# schematic.net
KiCad netlist of a schematic drawn in EAGLE
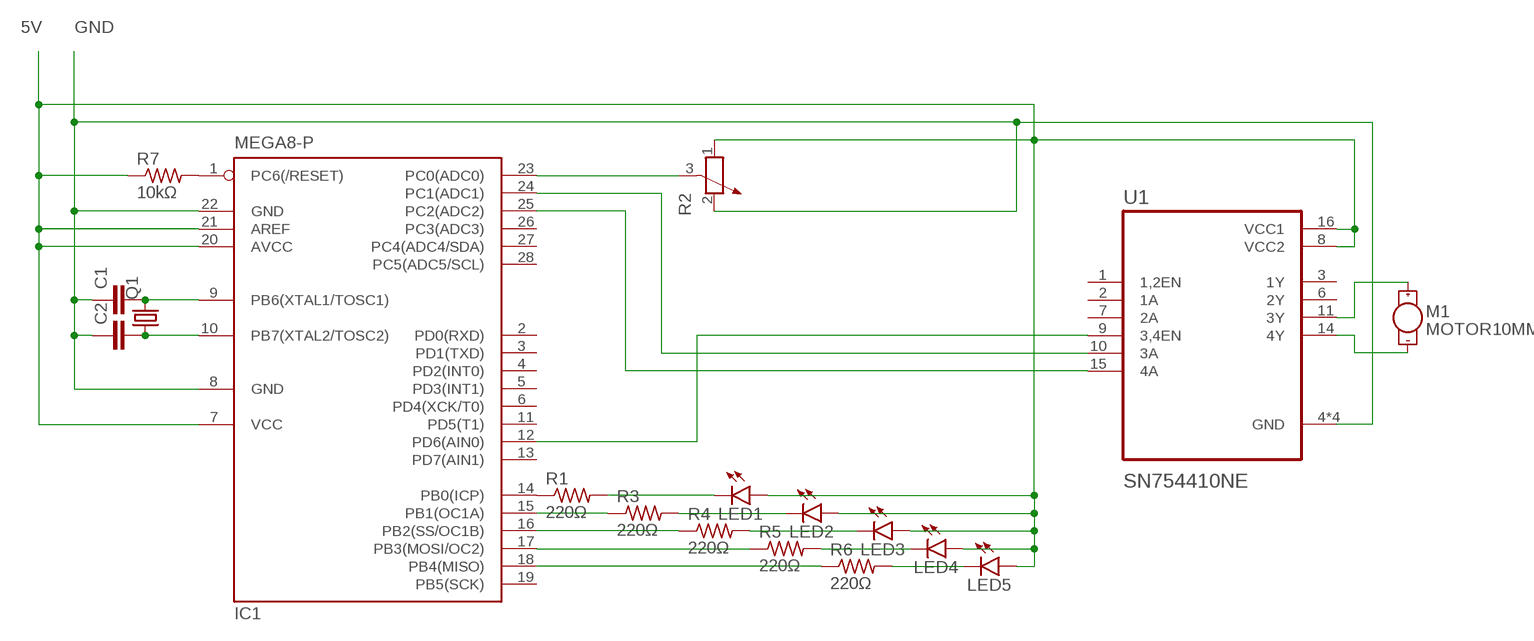
[diagram p0: schematic, sheet 1]

(export (version "E")
  (design (tool "Eeschema 10.0.6"))
  (components
    (comp (ref "C1")
      (value "C2,5-3")
      (footprint "eagle-import:C2.5-3")
      (libsource (lib "eagle-import") (part "C2,5-3"))
    )
    (comp (ref "C2")
      (value "C2,5-3")
      (footprint "eagle-import:C2.5-3")
      (libsource (lib "eagle-import") (part "C2,5-3"))
    )
    (comp (ref "IC1")
      (value "MEGA8-P")
      (footprint "eagle-import:DIL28-3")
      (libsource (lib "eagle-import") (part "MEGA8-P"))
    )
    (comp (ref "LED1")
      (value "LED")
      (footprint "eagle-import:SMARTLED-TTW")
      (libsource (lib "eagle-import") (part "LED"))
    )
    (comp (ref "LED2")
      (value "LED")
      (footprint "eagle-import:SMARTLED-TTW")
      (libsource (lib "eagle-import") (part "LED"))
    )
    (comp (ref "LED3")
      (value "LED")
      (footprint "eagle-import:SMARTLED-TTW")
      (libsource (lib "eagle-import") (part "LED"))
    )
    (comp (ref "LED4")
      (value "LED")
      (footprint "eagle-import:SMARTLED-TTW")
      (libsource (lib "eagle-import") (part "LED"))
    )
    (comp (ref "LED5")
      (value "LED")
      (footprint "eagle-import:SMARTLED-TTW")
      (libsource (lib "eagle-import") (part "LED"))
    )
    (comp (ref "M1")
      (value "MOTOR10MM")
      (footprint "eagle-import:VIBE-MOTOR-10MM")
      (libsource (lib "eagle-import") (part "MOTOR10MM"))
    )
    (comp (ref "Q1")
      (value "CRYSTALHC18U-V")
      (footprint "eagle-import:HC18U-V")
      (libsource (lib "eagle-import") (part "CRYSTALHC18U-V"))
    )
    (comp (ref "R1")
      (value "220Ω")
      (footprint "eagle-import:0204V")
      (libsource (lib "eagle-import") (part "R-US_0204/2V"))
    )
    (comp (ref "R2")
      (value "POTENTIOMETER_PT-10")
      (footprint "eagle-import:PT-10")
      (libsource (lib "eagle-import") (part "POTENTIOMETER_PT-10"))
    )
    (comp (ref "R3")
      (value "220Ω")
      (footprint "eagle-import:0204V")
      (libsource (lib "eagle-import") (part "R-US_0204/2V"))
    )
    (comp (ref "R4")
      (value "220Ω")
      (footprint "eagle-import:0204V")
      (libsource (lib "eagle-import") (part "R-US_0204/2V"))
    )
    (comp (ref "R5")
      (value "220Ω")
      (footprint "eagle-import:0204V")
      (libsource (lib "eagle-import") (part "R-US_0204/2V"))
    )
    (comp (ref "R6")
      (value "220Ω")
      (footprint "eagle-import:0204V")
      (libsource (lib "eagle-import") (part "R-US_0204/2V"))
    )
    (comp (ref "R7")
      (value "10kΩ")
      (footprint "eagle-import:0204V")
      (libsource (lib "eagle-import") (part "R-US_0204/2V"))
    )
    (comp (ref "U1")
      (value "SN754410NE")
      (footprint "eagle-import:DIP762W45P254L1980H508Q16")
      (fields (field (name "MF") "Texas Instruments"))
      (libsource (lib "eagle-import") (part "SN754410NE"))
    )
  )
  (nets
    (net (code "1") (name "/5V") (class "Default")
      (node (ref "IC1") (pin "20") (pinfunction "AVCC_20") (pintype "power_in"))
      (node (ref "IC1") (pin "21") (pinfunction "AREF_21") (pintype "passive"))
      (node (ref "IC1") (pin "7") (pinfunction "VCC_7") (pintype "power_in"))
      (node (ref "LED1") (pin "A@1") (pinfunction "A_A@1") (pintype "passive"))
      (node (ref "LED2") (pin "A@1") (pinfunction "A_A@1") (pintype "passive"))
      (node (ref "LED3") (pin "A@1") (pinfunction "A_A@1") (pintype "passive"))
      (node (ref "LED4") (pin "A@1") (pinfunction "A_A@1") (pintype "passive"))
      (node (ref "LED5") (pin "A@1") (pinfunction "A_A@1") (pintype "passive"))
      (node (ref "R2") (pin "1") (pinfunction "1_1") (pintype "passive"))
      (node (ref "R7") (pin "1") (pinfunction "1_1") (pintype "passive"))
      (node (ref "U1") (pin "16") (pinfunction "VCC1_16") (pintype "power_in"))
      (node (ref "U1") (pin "8") (pinfunction "VCC2_8") (pintype "power_in"))
    )
    (net (code "2") (name "/GND") (class "Default")
      (node (ref "C1") (pin "1") (pinfunction "1_1") (pintype "passive"))
      (node (ref "C2") (pin "1") (pinfunction "1_1") (pintype "passive"))
      (node (ref "IC1") (pin "22") (pinfunction "GND_22") (pintype "power_in"))
      (node (ref "IC1") (pin "8") (pinfunction "GND_8") (pintype "power_in"))
      (node (ref "R2") (pin "2") (pinfunction "2_2") (pintype "passive"))
      (node (ref "U1") (pin "12") (pinfunction "GND_12") (pintype "power_in"))
      (node (ref "U1") (pin "13") (pinfunction "GND_13") (pintype "power_in"))
      (node (ref "U1") (pin "4") (pinfunction "GND_4") (pintype "power_in"))
      (node (ref "U1") (pin "5") (pinfunction "GND_5") (pintype "power_in"))
    )
    (net (code "3") (name "Net-(IC1-PB0(ICP))") (class "Default")
      (node (ref "IC1") (pin "14") (pinfunction "PB0(ICP)_14") (pintype "bidirectional"))
      (node (ref "R1") (pin "1") (pinfunction "1_1") (pintype "passive"))
    )
    (net (code "4") (name "Net-(IC1-PB1(OC1A))") (class "Default")
      (node (ref "IC1") (pin "15") (pinfunction "PB1(OC1A)_15") (pintype "bidirectional"))
      (node (ref "R3") (pin "1") (pinfunction "1_1") (pintype "passive"))
    )
    (net (code "5") (name "Net-(IC1-PB2(SS{slash}OC1B))") (class "Default")
      (node (ref "IC1") (pin "16") (pinfunction "PB2(SS/OC1B)_16") (pintype "bidirectional"))
      (node (ref "R4") (pin "1") (pinfunction "1_1") (pintype "passive"))
    )
    (net (code "6") (name "Net-(IC1-PB3(MOSI{slash}OC2))") (class "Default")
      (node (ref "IC1") (pin "17") (pinfunction "PB3(MOSI/OC2)_17") (pintype "bidirectional"))
      (node (ref "R5") (pin "1") (pinfunction "1_1") (pintype "passive"))
    )
    (net (code "7") (name "Net-(IC1-PB4(MISO))") (class "Default")
      (node (ref "IC1") (pin "18") (pinfunction "PB4(MISO)_18") (pintype "bidirectional"))
      (node (ref "R6") (pin "1") (pinfunction "1_1") (pintype "passive"))
    )
    (net (code "8") (name "Net-(IC1-PB6(XTAL1{slash}TOSC1))") (class "Default")
      (node (ref "C1") (pin "2") (pinfunction "2_2") (pintype "passive"))
      (node (ref "IC1") (pin "9") (pinfunction "PB6(XTAL1/TOSC1)_9") (pintype "bidirectional"))
      (node (ref "Q1") (pin "2") (pinfunction "2_2") (pintype "passive"))
    )
    (net (code "9") (name "Net-(IC1-PB7(XTAL2{slash}TOSC2))") (class "Default")
      (node (ref "C2") (pin "2") (pinfunction "2_2") (pintype "passive"))
      (node (ref "IC1") (pin "10") (pinfunction "PB7(XTAL2/TOSC2)_10") (pintype "bidirectional"))
      (node (ref "Q1") (pin "1") (pinfunction "1_1") (pintype "passive"))
    )
    (net (code "10") (name "Net-(IC1-PC0(ADC0))") (class "Default")
      (node (ref "IC1") (pin "23") (pinfunction "PC0(ADC0)_23") (pintype "bidirectional"))
      (node (ref "R2") (pin "3") (pinfunction "3_3") (pintype "passive"))
    )
    (net (code "11") (name "Net-(IC1-PC1(ADC1))") (class "Default")
      (node (ref "IC1") (pin "24") (pinfunction "PC1(ADC1)_24") (pintype "bidirectional"))
      (node (ref "U1") (pin "10") (pinfunction "3A_10") (pintype "input"))
    )
    (net (code "12") (name "Net-(IC1-PC2(ADC2))") (class "Default")
      (node (ref "IC1") (pin "25") (pinfunction "PC2(ADC2)_25") (pintype "bidirectional"))
      (node (ref "U1") (pin "15") (pinfunction "4A_15") (pintype "input"))
    )
    (net (code "13") (name "Net-(IC1-PC6({slash}RESET))") (class "Default")
      (node (ref "IC1") (pin "1") (pinfunction "PC6(/RESET)_1") (pintype "bidirectional"))
      (node (ref "R7") (pin "2") (pinfunction "2_2") (pintype "passive"))
    )
    (net (code "14") (name "Net-(IC1-PD6(AIN0))") (class "Default")
      (node (ref "IC1") (pin "12") (pinfunction "PD6(AIN0)_12") (pintype "bidirectional"))
      (node (ref "U1") (pin "9") (pinfunction "3,4EN_9") (pintype "input"))
    )
    (net (code "15") (name "Net-(LED1-C)") (class "Default")
      (node (ref "LED1") (pin "C@1") (pinfunction "C_C@1") (pintype "passive"))
      (node (ref "R1") (pin "2") (pinfunction "2_2") (pintype "passive"))
    )
    (net (code "16") (name "Net-(LED2-C)") (class "Default")
      (node (ref "LED2") (pin "C@1") (pinfunction "C_C@1") (pintype "passive"))
      (node (ref "R3") (pin "2") (pinfunction "2_2") (pintype "passive"))
    )
    (net (code "17") (name "Net-(LED3-C)") (class "Default")
      (node (ref "LED3") (pin "C@1") (pinfunction "C_C@1") (pintype "passive"))
      (node (ref "R4") (pin "2") (pinfunction "2_2") (pintype "passive"))
    )
    (net (code "18") (name "Net-(LED4-C)") (class "Default")
      (node (ref "LED4") (pin "C@1") (pinfunction "C_C@1") (pintype "passive"))
      (node (ref "R5") (pin "2") (pinfunction "2_2") (pintype "passive"))
    )
    (net (code "19") (name "Net-(LED5-C)") (class "Default")
      (node (ref "LED5") (pin "C@1") (pinfunction "C_C@1") (pintype "passive"))
      (node (ref "R6") (pin "2") (pinfunction "2_2") (pintype "passive"))
    )
    (net (code "20") (name "Net-(U1-3Y)") (class "Default")
      (node (ref "M1") (pin "+") (pinfunction "+_+") (pintype "bidirectional"))
      (node (ref "U1") (pin "11") (pinfunction "3Y_11") (pintype "output"))
    )
    (net (code "21") (name "Net-(U1-4Y)") (class "Default")
      (node (ref "M1") (pin "-") (pinfunction "-_-") (pintype "bidirectional"))
      (node (ref "U1") (pin "14") (pinfunction "4Y_14") (pintype "output"))
    )
    (net (code "22") (name "unconnected-(IC1-PB5(SCK)-Pad19)") (class "Default")
      (node (ref "IC1") (pin "19") (pinfunction "PB5(SCK)_19") (pintype "bidirectional"))
    )
    (net (code "23") (name "unconnected-(IC1-PC3(ADC3)-Pad26)") (class "Default")
      (node (ref "IC1") (pin "26") (pinfunction "PC3(ADC3)_26") (pintype "bidirectional"))
    )
    (net (code "24") (name "unconnected-(IC1-PC4(ADC4{slash}SDA)-Pad27)") (class "Default")
      (node (ref "IC1") (pin "27") (pinfunction "PC4(ADC4/SDA)_27") (pintype "bidirectional"))
    )
    (net (code "25") (name "unconnected-(IC1-PC5(ADC5{slash}SCL)-Pad28)") (class "Default")
      (node (ref "IC1") (pin "28") (pinfunction "PC5(ADC5/SCL)_28") (pintype "bidirectional"))
    )
    (net (code "26") (name "unconnected-(IC1-PD0(RXD)-Pad2)") (class "Default")
      (node (ref "IC1") (pin "2") (pinfunction "PD0(RXD)_2") (pintype "bidirectional"))
    )
    (net (code "27") (name "unconnected-(IC1-PD1(TXD)-Pad3)") (class "Default")
      (node (ref "IC1") (pin "3") (pinfunction "PD1(TXD)_3") (pintype "bidirectional"))
    )
    (net (code "28") (name "unconnected-(IC1-PD2(INT0)-Pad4)") (class "Default")
      (node (ref "IC1") (pin "4") (pinfunction "PD2(INT0)_4") (pintype "bidirectional"))
    )
    (net (code "29") (name "unconnected-(IC1-PD3(INT1)-Pad5)") (class "Default")
      (node (ref "IC1") (pin "5") (pinfunction "PD3(INT1)_5") (pintype "bidirectional"))
    )
    (net (code "30") (name "unconnected-(IC1-PD4(XCK{slash}T0)-Pad6)") (class "Default")
      (node (ref "IC1") (pin "6") (pinfunction "PD4(XCK/T0)_6") (pintype "bidirectional"))
    )
    (net (code "31") (name "unconnected-(IC1-PD5(T1)-Pad11)") (class "Default")
      (node (ref "IC1") (pin "11") (pinfunction "PD5(T1)_11") (pintype "bidirectional"))
    )
    (net (code "32") (name "unconnected-(IC1-PD7(AIN1)-Pad13)") (class "Default")
      (node (ref "IC1") (pin "13") (pinfunction "PD7(AIN1)_13") (pintype "bidirectional"))
    )
    (net (code "33") (name "unconnected-(U1-1,2EN-Pad1)") (class "Default")
      (node (ref "U1") (pin "1") (pinfunction "1,2EN_1") (pintype "input"))
    )
    (net (code "34") (name "unconnected-(U1-1A-Pad2)") (class "Default")
      (node (ref "U1") (pin "2") (pinfunction "1A_2") (pintype "input"))
    )
    (net (code "35") (name "unconnected-(U1-1Y-Pad3)") (class "Default")
      (node (ref "U1") (pin "3") (pinfunction "1Y_3") (pintype "output"))
    )
    (net (code "36") (name "unconnected-(U1-2A-Pad7)") (class "Default")
      (node (ref "U1") (pin "7") (pinfunction "2A_7") (pintype "input"))
    )
    (net (code "37") (name "unconnected-(U1-2Y-Pad6)") (class "Default")
      (node (ref "U1") (pin "6") (pinfunction "2Y_6") (pintype "output"))
    )
  )
)
